# Sensors.net
KiCad netlist of a schematic drawn in Altium Designer
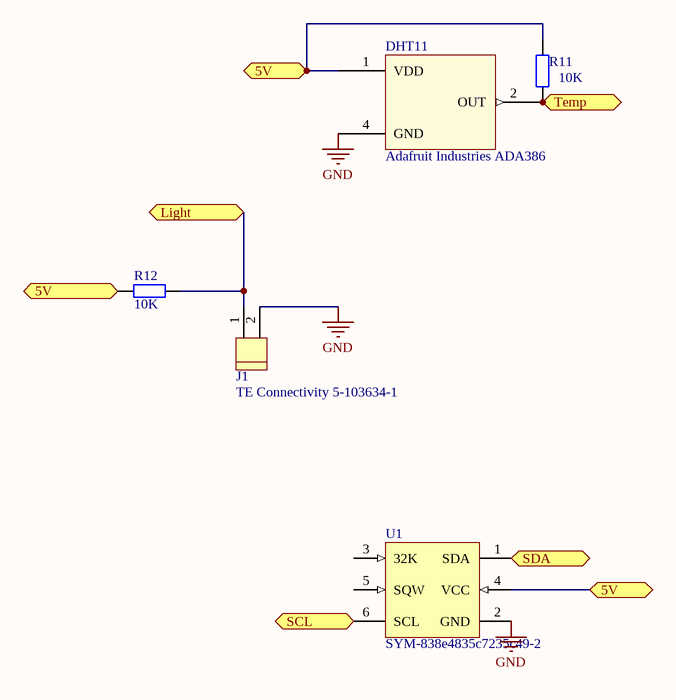
[diagram p0: Sensors.SchDoc]

(export (version "E")
  (design (tool "Eeschema 10.0.6"))
  (components
    (comp (ref "DHT11")
      (value "Adafruit Industries ADA386")
      (footprint "DHT11")
      (description "DHT11 basic temperature-humidity sensor + extras")
      (fields (field (name "MANUFACTURER PART NUMBER") "ADA386"))
      (libsource (lib "CommunityVault") (part "CMP-f2473ad10e112d80-1"))
    )
    (comp (ref "J1")
      (value "TE Connectivity 5-103634-1")
      (footprint "PCB-uaeje0c37wq92n4bv9j3-1")
      (description "CONN HEADER RTANG 2POS PCB TIN")
      (libsource (lib "CommunityVault") (part "SYM-6cb9a7e820d6b37e-1"))
    )
    (comp (ref "R11")
      (value "Res2")
      (footprint "PCB-mctr3h3tvednl0z90ud0-1")
      (description "Resistor; Carbon Composition; Res 3.9 Kilohms; Pwr-Rtg 0.25 W; Tol 5%; Axial")
      (fields (field (name "MANUFACTURER PART NUMBER") "OD392JE") (field (name "OHMS") "10K"))
      (libsource (lib "") (part "CMP-1413dd18cda2cbd4-1_1"))
    )
    (comp (ref "R12")
      (value "Res2")
      (footprint "PCB-mctr3h3tvednl0z90ud0-1")
      (description "Resistor; Carbon Composition; Res 3.9 Kilohms; Pwr-Rtg 0.25 W; Tol 5%; Axial")
      (fields (field (name "MANUFACTURER PART NUMBER") "OD392JE") (field (name "OHMS") "10K"))
      (libsource (lib "CommunityVault") (part "CMP-1413dd18cda2cbd4-1"))
    )
    (comp (ref "U1")
      (value "SYM-838e4835c7235c49-2")
      (footprint "PCB-y0s4izvblyw4j4eze3nd-1")
      (description "Peripheral Module, DS3231M I2C Real-Time Clock")
      (fields (field (name "MANUFACTURER PART NUMBER") "DS3231MPMB1#"))
      (libsource (lib "CommunityVault") (part "SYM-838e4835c7235c49-2"))
    )
  )
  (nets
    (net (code "1") (name "/5V") (class "Default")
      (node (ref "DHT11") (pin "1") (pinfunction "VDD_1") (pintype "power_in"))
      (node (ref "R11") (pin "2") (pinfunction "2_2") (pintype "passive"))
      (node (ref "R12") (pin "2") (pinfunction "2_2") (pintype "passive"))
      (node (ref "U1") (pin "4") (pinfunction "VCC_4") (pintype "input"))
    )
    (net (code "2") (name "/Light") (class "Default")
      (node (ref "J1") (pin "1") (pinfunction "1_1") (pintype "passive"))
      (node (ref "R12") (pin "1") (pinfunction "1_1") (pintype "passive"))
    )
    (net (code "3") (name "/SCL") (class "Default")
      (node (ref "U1") (pin "6") (pinfunction "SCL_6") (pintype "power_in"))
    )
    (net (code "4") (name "/SDA") (class "Default")
      (node (ref "U1") (pin "1") (pinfunction "SDA_1") (pintype "tri_state"))
    )
    (net (code "5") (name "/Temp") (class "Default")
      (node (ref "DHT11") (pin "2") (pinfunction "OUT_2") (pintype "output"))
      (node (ref "R11") (pin "1") (pinfunction "1_1") (pintype "passive"))
    )
    (net (code "6") (name "GND") (class "Default")
      (node (ref "DHT11") (pin "4") (pinfunction "GND_4") (pintype "power_in"))
      (node (ref "J1") (pin "2") (pinfunction "2_2") (pintype "passive"))
      (node (ref "U1") (pin "2") (pinfunction "GND_2") (pintype "power_in"))
    )
    (net (code "7") (name "unconnected-(U1-32K-Pad3)") (class "Default")
      (node (ref "U1") (pin "3") (pinfunction "32K_3") (pintype "input"))
    )
    (net (code "8") (name "unconnected-(U1-SQW-Pad5)") (class "Default")
      (node (ref "U1") (pin "5") (pinfunction "SQW_5") (pintype "input"))
    )
  )
)
